# Keg_Cop_-_RJ45_-_6-Pack.net
KiCad netlist of a schematic drawn in EAGLE
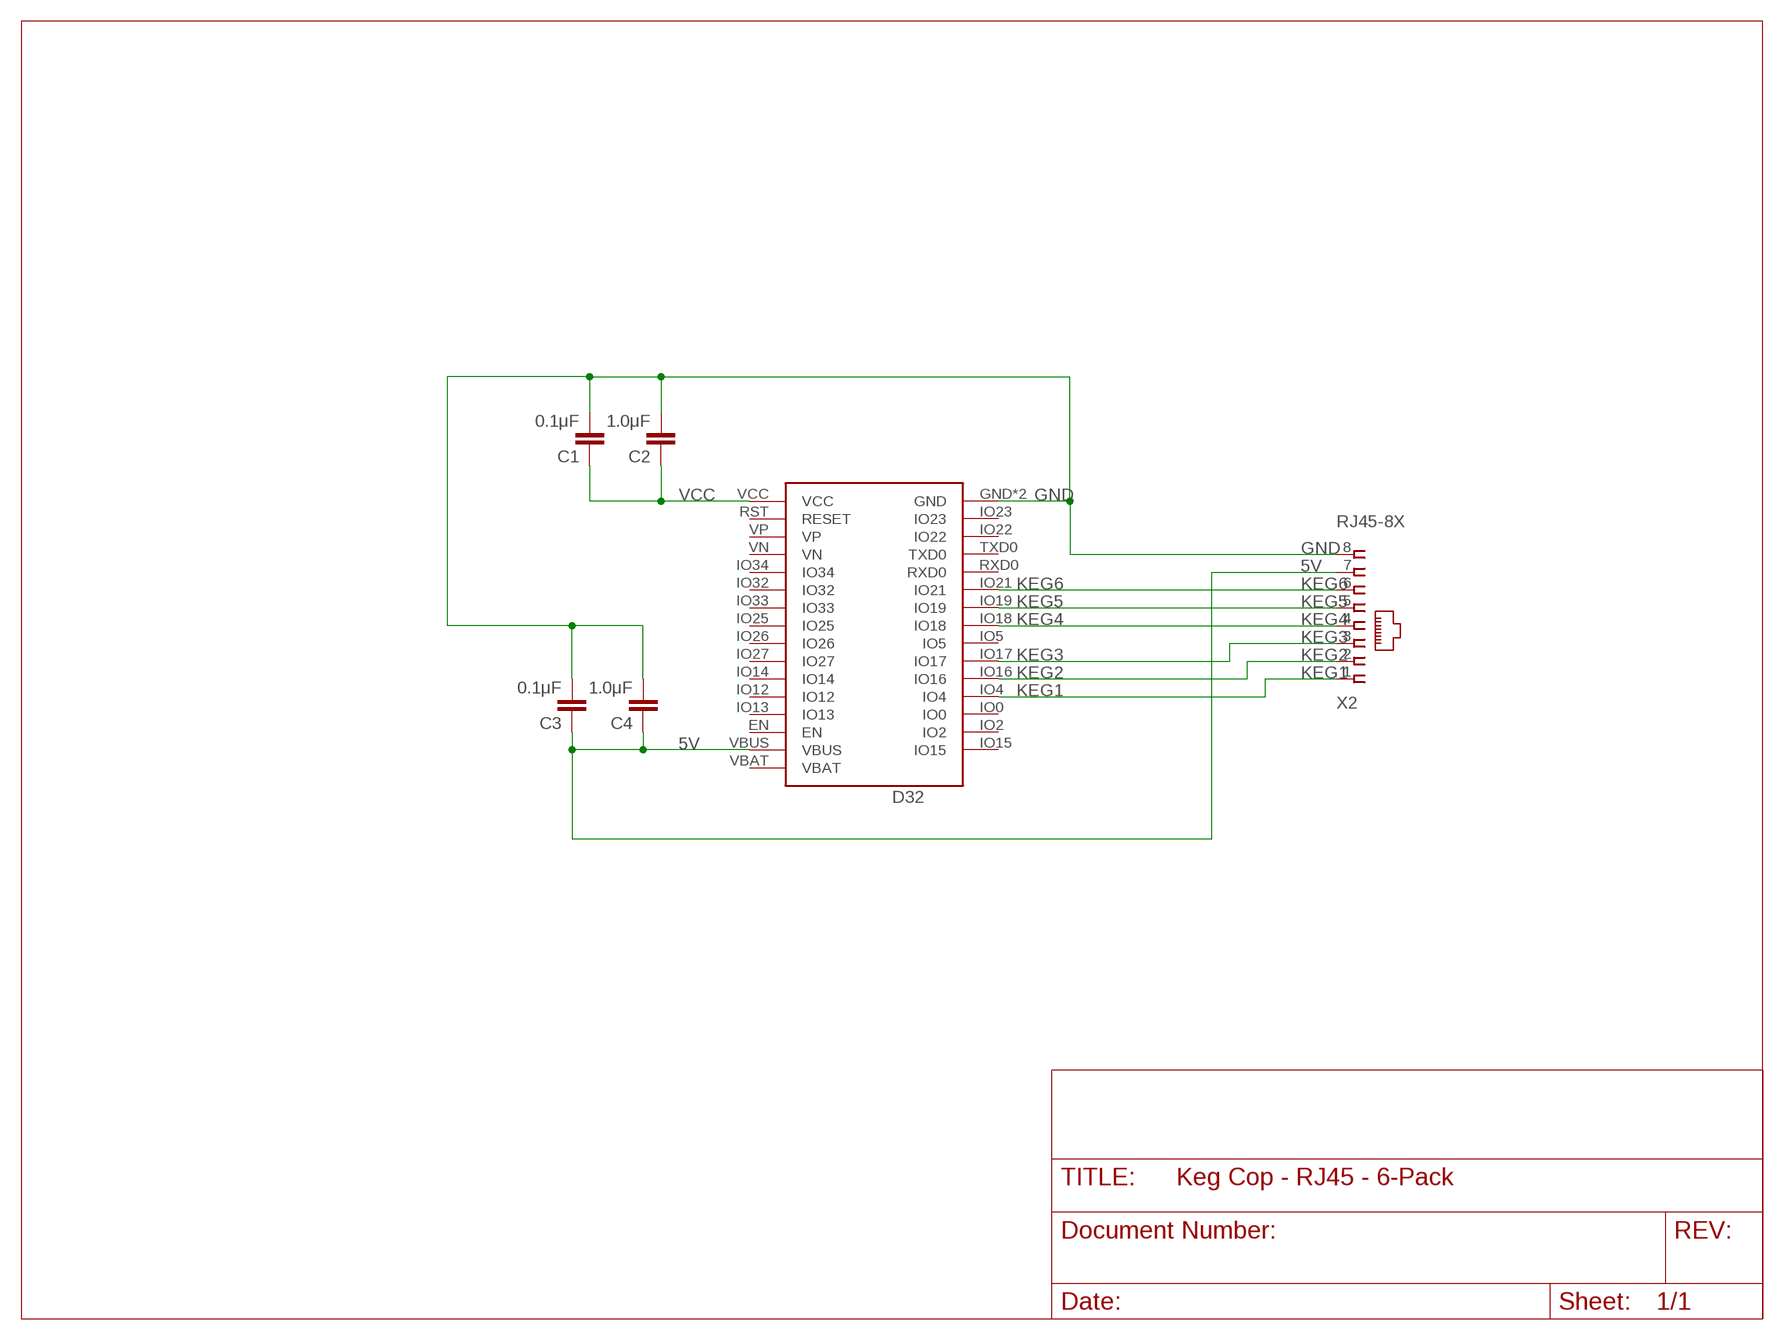
[diagram p0: schematic, sheet 1]

(export (version "E")
  (design (tool "Eeschema 10.0.6"))
  (components
    (comp (ref "C1")
      (value "0.1μF")
      (footprint "eagle-import:CAP_PTH-2.54")
      (libsource (lib "eagle-import") (part "CAP_CERAMIC_2.54"))
    )
    (comp (ref "C2")
      (value "1.0μF")
      (footprint "eagle-import:CAP_PTH-2.54")
      (libsource (lib "eagle-import") (part "CAP_CERAMIC_2.54"))
    )
    (comp (ref "C3")
      (value "0.1μF")
      (footprint "eagle-import:CAP_PTH-2.54")
      (libsource (lib "eagle-import") (part "CAP_CERAMIC_2.54"))
    )
    (comp (ref "C4")
      (value "1.0μF")
      (footprint "eagle-import:CAP_PTH-2.54")
      (libsource (lib "eagle-import") (part "CAP_CERAMIC_2.54"))
    )
    (comp (ref "D32")
      (value "Lolin D32")
      (footprint "eagle-import:D32_NO_BATT")
      (libsource (lib "eagle-import") (part "WEMOS-D32D32_NO_BATT"))
    )
    (comp (ref "X2")
      (value "RJ45-8X")
      (footprint "eagle-import:RJ45-NO-SHIELD")
      (libsource (lib "eagle-import") (part "RJ45-8X"))
    )
  )
  (nets
    (net (code "1") (name "/5V") (class "Default")
      (node (ref "C3") (pin "1") (pinfunction "1_1") (pintype "passive"))
      (node (ref "C4") (pin "1") (pinfunction "1_1") (pintype "passive"))
      (node (ref "D32") (pin "VBUS") (pinfunction "VBUS_VBUS") (pintype "bidirectional"))
      (node (ref "X2") (pin "7") (pinfunction "7_7") (pintype "passive"))
    )
    (net (code "2") (name "/GND") (class "Default")
      (node (ref "C1") (pin "2") (pinfunction "2_2") (pintype "passive"))
      (node (ref "C2") (pin "2") (pinfunction "2_2") (pintype "passive"))
      (node (ref "C3") (pin "2") (pinfunction "2_2") (pintype "passive"))
      (node (ref "C4") (pin "2") (pinfunction "2_2") (pintype "passive"))
      (node (ref "D32") (pin "GND") (pinfunction "GND_GND") (pintype "power_in"))
      (node (ref "D32") (pin "GND2") (pinfunction "GND_GND2") (pintype "power_in"))
      (node (ref "X2") (pin "8") (pinfunction "8_8") (pintype "passive"))
    )
    (net (code "3") (name "/KEG1") (class "Default")
      (node (ref "D32") (pin "IO4") (pinfunction "IO4_IO4") (pintype "bidirectional"))
      (node (ref "X2") (pin "1") (pinfunction "1_1") (pintype "passive"))
    )
    (net (code "4") (name "/KEG2") (class "Default")
      (node (ref "D32") (pin "IO16") (pinfunction "IO16_IO16") (pintype "bidirectional"))
      (node (ref "X2") (pin "2") (pinfunction "2_2") (pintype "passive"))
    )
    (net (code "5") (name "/KEG3") (class "Default")
      (node (ref "D32") (pin "IO17") (pinfunction "IO17_IO17") (pintype "bidirectional"))
      (node (ref "X2") (pin "3") (pinfunction "3_3") (pintype "passive"))
    )
    (net (code "6") (name "/KEG4") (class "Default")
      (node (ref "D32") (pin "IO18") (pinfunction "IO18_IO18") (pintype "bidirectional"))
      (node (ref "X2") (pin "4") (pinfunction "4_4") (pintype "passive"))
    )
    (net (code "7") (name "/KEG5") (class "Default")
      (node (ref "D32") (pin "IO19") (pinfunction "IO19_IO19") (pintype "bidirectional"))
      (node (ref "X2") (pin "5") (pinfunction "5_5") (pintype "passive"))
    )
    (net (code "8") (name "/KEG6") (class "Default")
      (node (ref "D32") (pin "IO21") (pinfunction "IO21_IO21") (pintype "bidirectional"))
      (node (ref "X2") (pin "6") (pinfunction "6_6") (pintype "passive"))
    )
    (net (code "9") (name "/VCC") (class "Default")
      (node (ref "C1") (pin "1") (pinfunction "1_1") (pintype "passive"))
      (node (ref "C2") (pin "1") (pinfunction "1_1") (pintype "passive"))
      (node (ref "D32") (pin "VCC") (pinfunction "VCC_VCC") (pintype "power_in"))
    )
    (net (code "10") (name "unconnected-(D32-PadEN)") (class "Default")
      (node (ref "D32") (pin "EN") (pinfunction "EN_EN") (pintype "bidirectional"))
    )
    (net (code "11") (name "unconnected-(D32-PadIO0)") (class "Default")
      (node (ref "D32") (pin "IO0") (pinfunction "IO0_IO0") (pintype "bidirectional"))
    )
    (net (code "12") (name "unconnected-(D32-PadIO2)") (class "Default")
      (node (ref "D32") (pin "IO2") (pinfunction "IO2_IO2") (pintype "bidirectional"))
    )
    (net (code "13") (name "unconnected-(D32-PadIO5)") (class "Default")
      (node (ref "D32") (pin "IO5") (pinfunction "IO5_IO5") (pintype "bidirectional"))
    )
    (net (code "14") (name "unconnected-(D32-PadIO12)") (class "Default")
      (node (ref "D32") (pin "IO12") (pinfunction "IO12_IO12") (pintype "bidirectional"))
    )
    (net (code "15") (name "unconnected-(D32-PadIO13)") (class "Default")
      (node (ref "D32") (pin "IO13") (pinfunction "IO13_IO13") (pintype "bidirectional"))
    )
    (net (code "16") (name "unconnected-(D32-PadIO14)") (class "Default")
      (node (ref "D32") (pin "IO14") (pinfunction "IO14_IO14") (pintype "bidirectional"))
    )
    (net (code "17") (name "unconnected-(D32-PadIO15)") (class "Default")
      (node (ref "D32") (pin "IO15") (pinfunction "IO15_IO15") (pintype "bidirectional"))
    )
    (net (code "18") (name "unconnected-(D32-PadIO22)") (class "Default")
      (node (ref "D32") (pin "IO22") (pinfunction "IO22_IO22") (pintype "bidirectional"))
    )
    (net (code "19") (name "unconnected-(D32-PadIO23)") (class "Default")
      (node (ref "D32") (pin "IO23") (pinfunction "IO23_IO23") (pintype "bidirectional"))
    )
    (net (code "20") (name "unconnected-(D32-PadIO25)") (class "Default")
      (node (ref "D32") (pin "IO25") (pinfunction "IO25_IO25") (pintype "bidirectional"))
    )
    (net (code "21") (name "unconnected-(D32-PadIO26)") (class "Default")
      (node (ref "D32") (pin "IO26") (pinfunction "IO26_IO26") (pintype "bidirectional"))
    )
    (net (code "22") (name "unconnected-(D32-PadIO27)") (class "Default")
      (node (ref "D32") (pin "IO27") (pinfunction "IO27_IO27") (pintype "bidirectional"))
    )
    (net (code "23") (name "unconnected-(D32-PadIO32)") (class "Default")
      (node (ref "D32") (pin "IO32") (pinfunction "IO32_IO32") (pintype "bidirectional"))
    )
    (net (code "24") (name "unconnected-(D32-PadIO33)") (class "Default")
      (node (ref "D32") (pin "IO33") (pinfunction "IO33_IO33") (pintype "bidirectional"))
    )
    (net (code "25") (name "unconnected-(D32-PadIO34)") (class "Default")
      (node (ref "D32") (pin "IO34") (pinfunction "IO34_IO34") (pintype "bidirectional"))
    )
    (net (code "26") (name "unconnected-(D32-PadRXD0)") (class "Default")
      (node (ref "D32") (pin "RXD0") (pinfunction "RXD0_RXD0") (pintype "input"))
    )
    (net (code "27") (name "unconnected-(D32-PadTXD0)") (class "Default")
      (node (ref "D32") (pin "TXD0") (pinfunction "TXD0_TXD0") (pintype "output"))
    )
    (net (code "28") (name "unconnected-(D32-PadVBAT)") (class "Default")
      (node (ref "D32") (pin "VBAT") (pinfunction "VBAT_VBAT") (pintype "bidirectional"))
    )
    (net (code "29") (name "unconnected-(D32-PadVN)") (class "Default")
      (node (ref "D32") (pin "VN") (pinfunction "VN_VN") (pintype "bidirectional"))
    )
    (net (code "30") (name "unconnected-(D32-PadVP)") (class "Default")
      (node (ref "D32") (pin "VP") (pinfunction "VP_VP") (pintype "bidirectional"))
    )
    (net (code "31") (name "unconnected-(D32-RESET-PadRST)") (class "Default")
      (node (ref "D32") (pin "RST") (pinfunction "RESET_RST") (pintype "bidirectional"))
    )
  )
)
